# BreakoutPcb.net
KiCad netlist of a schematic drawn in Altium Designer
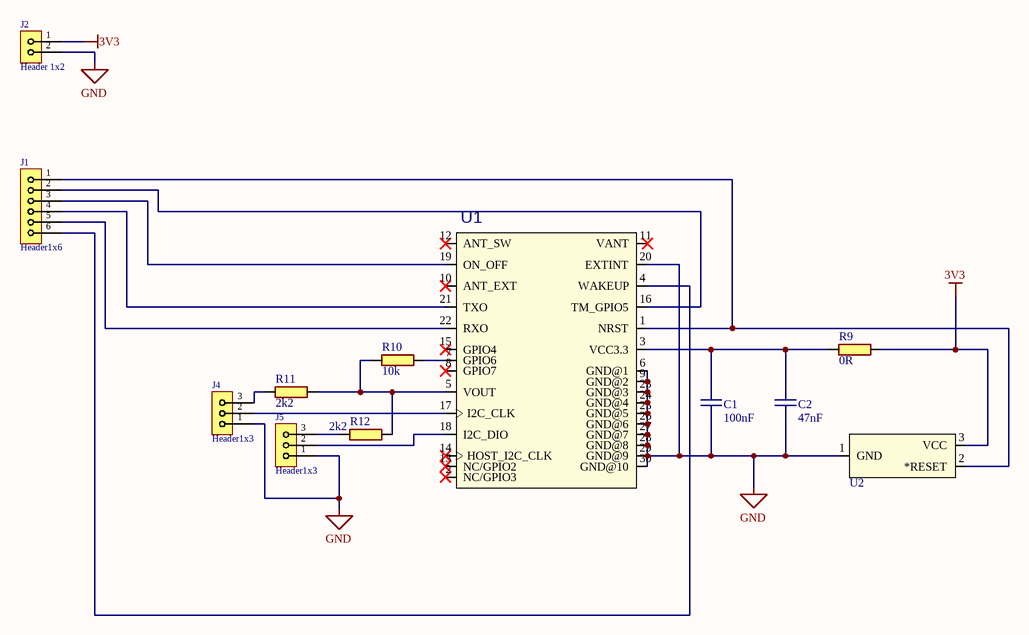
[diagram p0: BreakoutPcb.SchDoc]

(export (version "E")
  (design (tool "Eeschema 10.0.6"))
  (components
    (comp (ref "C1")
      (value "100nF")
      (footprint "CAPC0603(1608)55_N")
      (description "X7R 50V 5%")
      (libsource (lib "OVLib") (part "CAP"))
    )
    (comp (ref "C2")
      (value "47nF")
      (footprint "CAPC0805(2012)100_N")
      (description "X7R")
      (libsource (lib "OVLib") (part "CAP"))
    )
    (comp (ref "J1")
      (value "Header1x6")
      (footprint "HDRV6W64P254_1X6_1524X254X900B")
      (libsource (lib "OVLib") (part "Header1x6"))
    )
    (comp (ref "J2")
      (value "Header 1x2")
      (footprint "HDRV2W64P254_1X2_508X254X900B")
      (libsource (lib "OVLib") (part "Header1x2"))
    )
    (comp (ref "J4")
      (value "Header1x3")
      (footprint "HDRV3W64P254_1X3_762X254X900B")
      (libsource (lib "OVLib") (part "Header1x3"))
    )
    (comp (ref "J5")
      (value "Header1x3")
      (footprint "HDRV3W64P254_1X3_762X254X900B")
      (libsource (lib "OVLib") (part "Header1x3"))
    )
    (comp (ref "R9")
      (value "0R")
      (footprint "RESC0603(1608)_N")
      (description "0.1W 1% Thick film resistor")
      (libsource (lib "OVLib") (part "Resistor2"))
    )
    (comp (ref "R10")
      (value "10k")
      (footprint "RESC0603(1608)_N")
      (description "0.1W 1% Thick film resistor")
      (libsource (lib "OVLib") (part "Resistor2"))
    )
    (comp (ref "R11")
      (value "2k2")
      (footprint "RESC0603(1608)_N")
      (description "0.1W 1% Thick film resistor")
      (libsource (lib "OVLib") (part "Resistor2"))
    )
    (comp (ref "R12")
      (value "2k2")
      (footprint "RESC0603(1608)_N")
      (description "0.1W 1% Thick film resistor")
      (libsource (lib "OVLib") (part "Resistor2"))
    )
    (comp (ref "U1")
      (value "A2235-H")
      (footprint "XCVR_A2235-H")
      (description "Gps Module, Mini Outline w/ Ant")
      (fields (field (name "MF") "Maestro Wireless"))
      (libsource (lib "A2235-H") (part "A2235-H"))
    )
    (comp (ref "U2")
      (value "MAX809SEXR-T")
      (footprint "21-0075D")
      (description "PMIC - system monitor Maxim Integrated MAX809SEXR+T Reset/power-on reset SC 70 3")
      (fields (field (name "MP") "MAX809SEXR+T") (field (name "MF") "Maxim Integrated"))
      (libsource (lib "MAX809SEXR-T") (part "MAX809SEXR-T"))
    )
  )
  (nets
    (net (code "1") (name "3V3") (class "Default")
      (node (ref "J2") (pin "1") (pinfunction "1_1") (pintype "passive"))
      (node (ref "R9") (pin "2") (pinfunction "2_2") (pintype "passive"))
      (node (ref "U2") (pin "3") (pinfunction "VCC_3") (pintype "power_in"))
    )
    (net (code "2") (name "GND") (class "Default")
      (node (ref "C1") (pin "1") (pinfunction "1_1") (pintype "passive"))
      (node (ref "C2") (pin "1") (pinfunction "1_1") (pintype "passive"))
      (node (ref "J2") (pin "2") (pinfunction "2_2") (pintype "passive"))
      (node (ref "J4") (pin "1") (pinfunction "1_1") (pintype "passive"))
      (node (ref "J5") (pin "1") (pinfunction "1_1") (pintype "passive"))
      (node (ref "U1") (pin "20") (pinfunction "EXTINT_20") (pintype "input"))
      (node (ref "U1") (pin "23") (pinfunction "GND@3_23") (pintype "power_in"))
      (node (ref "U1") (pin "24") (pinfunction "GND@4_24") (pintype "power_in"))
      (node (ref "U1") (pin "25") (pinfunction "GND@5_25") (pintype "power_in"))
      (node (ref "U1") (pin "26") (pinfunction "GND@6_26") (pintype "power_in"))
      (node (ref "U1") (pin "27") (pinfunction "GND@7_27") (pintype "power_in"))
      (node (ref "U1") (pin "28") (pinfunction "GND@8_28") (pintype "power_in"))
      (node (ref "U1") (pin "29") (pinfunction "GND@9_29") (pintype "power_in"))
      (node (ref "U1") (pin "30") (pinfunction "GND@10_30") (pintype "power_in"))
      (node (ref "U1") (pin "6") (pinfunction "GND@1_6") (pintype "power_in"))
      (node (ref "U1") (pin "9") (pinfunction "GND@2_9") (pintype "power_in"))
      (node (ref "U2") (pin "1") (pinfunction "GND_1") (pintype "power_in"))
    )
    (net (code "3") (name "Net-(J4-Pad3)") (class "Default")
      (node (ref "J4") (pin "3") (pinfunction "3_3") (pintype "passive"))
      (node (ref "R11") (pin "1") (pinfunction "1_1") (pintype "passive"))
    )
    (net (code "4") (name "Net-(J5-Pad3)") (class "Default")
      (node (ref "J5") (pin "3") (pinfunction "3_3") (pintype "passive"))
      (node (ref "R12") (pin "1") (pinfunction "1_1") (pintype "passive"))
    )
    (net (code "5") (name "Net-(U1-GPIO6)") (class "Default")
      (node (ref "R10") (pin "2") (pinfunction "2_2") (pintype "passive"))
      (node (ref "U1") (pin "7") (pinfunction "GPIO6_7") (pintype "input"))
    )
    (net (code "6") (name "Net-(U1-I2C_CLK)") (class "Default")
      (node (ref "J4") (pin "2") (pinfunction "2_2") (pintype "passive"))
      (node (ref "U1") (pin "17") (pinfunction "I2C_CLK_17") (pintype "bidirectional"))
    )
    (net (code "7") (name "Net-(U1-I2C_DIO)") (class "Default")
      (node (ref "J5") (pin "2") (pinfunction "2_2") (pintype "passive"))
      (node (ref "U1") (pin "18") (pinfunction "I2C_DIO_18") (pintype "bidirectional"))
    )
    (net (code "8") (name "Net-(U1-NRST)") (class "Default")
      (node (ref "J1") (pin "1") (pinfunction "1_1") (pintype "passive"))
      (node (ref "U1") (pin "1") (pinfunction "NRST_1") (pintype "input"))
      (node (ref "U2") (pin "2") (pinfunction "*RESET_2") (pintype "output"))
    )
    (net (code "9") (name "Net-(U1-ON_OFF)") (class "Default")
      (node (ref "J1") (pin "3") (pinfunction "3_3") (pintype "passive"))
      (node (ref "U1") (pin "19") (pinfunction "ON_OFF_19") (pintype "input"))
    )
    (net (code "10") (name "Net-(U1-RXO)") (class "Default")
      (node (ref "J1") (pin "5") (pinfunction "5_5") (pintype "passive"))
      (node (ref "U1") (pin "22") (pinfunction "RXO_22") (pintype "input"))
    )
    (net (code "11") (name "Net-(U1-TM_GPIO5)") (class "Default")
      (node (ref "J1") (pin "2") (pinfunction "2_2") (pintype "passive"))
      (node (ref "U1") (pin "16") (pinfunction "TM_GPIO5_16") (pintype "output"))
    )
    (net (code "12") (name "Net-(U1-TXO)") (class "Default")
      (node (ref "J1") (pin "4") (pinfunction "4_4") (pintype "passive"))
      (node (ref "U1") (pin "21") (pinfunction "TXO_21") (pintype "output"))
    )
    (net (code "13") (name "Net-(U1-VCC3.3)") (class "Default")
      (node (ref "C1") (pin "2") (pinfunction "2_2") (pintype "passive"))
      (node (ref "C2") (pin "2") (pinfunction "2_2") (pintype "passive"))
      (node (ref "R9") (pin "1") (pinfunction "1_1") (pintype "passive"))
      (node (ref "U1") (pin "3") (pinfunction "VCC3.3_3") (pintype "power_in"))
    )
    (net (code "14") (name "Net-(U1-VOUT)") (class "Default")
      (node (ref "R10") (pin "1") (pinfunction "1_1") (pintype "passive"))
      (node (ref "R11") (pin "2") (pinfunction "2_2") (pintype "passive"))
      (node (ref "R12") (pin "2") (pinfunction "2_2") (pintype "passive"))
      (node (ref "U1") (pin "5") (pinfunction "VOUT_5") (pintype "output"))
    )
    (net (code "15") (name "Net-(U1-WAKEUP)") (class "Default")
      (node (ref "J1") (pin "6") (pinfunction "6_6") (pintype "passive"))
      (node (ref "U1") (pin "4") (pinfunction "WAKEUP_4") (pintype "output"))
    )
    (net (code "16") (name "unconnected-(U1-ANT_EXT-Pad10)") (class "Default")
      (node (ref "U1") (pin "10") (pinfunction "ANT_EXT_10") (pintype "input+no_connect"))
    )
    (net (code "17") (name "unconnected-(U1-ANT_SW-Pad12)") (class "Default")
      (node (ref "U1") (pin "12") (pinfunction "ANT_SW_12") (pintype "input+no_connect"))
    )
    (net (code "18") (name "unconnected-(U1-GPIO4-Pad15)") (class "Default")
      (node (ref "U1") (pin "15") (pinfunction "GPIO4_15") (pintype "input+no_connect"))
    )
    (net (code "19") (name "unconnected-(U1-GPIO7-Pad8)") (class "Default")
      (node (ref "U1") (pin "8") (pinfunction "GPIO7_8") (pintype "input+no_connect"))
    )
    (net (code "20") (name "unconnected-(U1-HOST_I2C_CLK-Pad14)") (class "Default")
      (node (ref "U1") (pin "14") (pinfunction "HOST_I2C_CLK_14") (pintype "bidirectional+no_connect"))
    )
    (net (code "21") (name "unconnected-(U1-NC{slash}GPIO2-Pad13)") (class "Default")
      (node (ref "U1") (pin "13") (pinfunction "NC/GPIO2_13") (pintype "bidirectional+no_connect"))
    )
    (net (code "22") (name "unconnected-(U1-NC{slash}GPIO3-Pad2)") (class "Default")
      (node (ref "U1") (pin "2") (pinfunction "NC/GPIO3_2") (pintype "bidirectional+no_connect"))
    )
    (net (code "23") (name "unconnected-(U1-VANT-Pad11)") (class "Default")
      (node (ref "U1") (pin "11") (pinfunction "VANT_11") (pintype "power_in+no_connect"))
    )
  )
)
